# me433.net
KiCad netlist of a schematic drawn in EAGLE
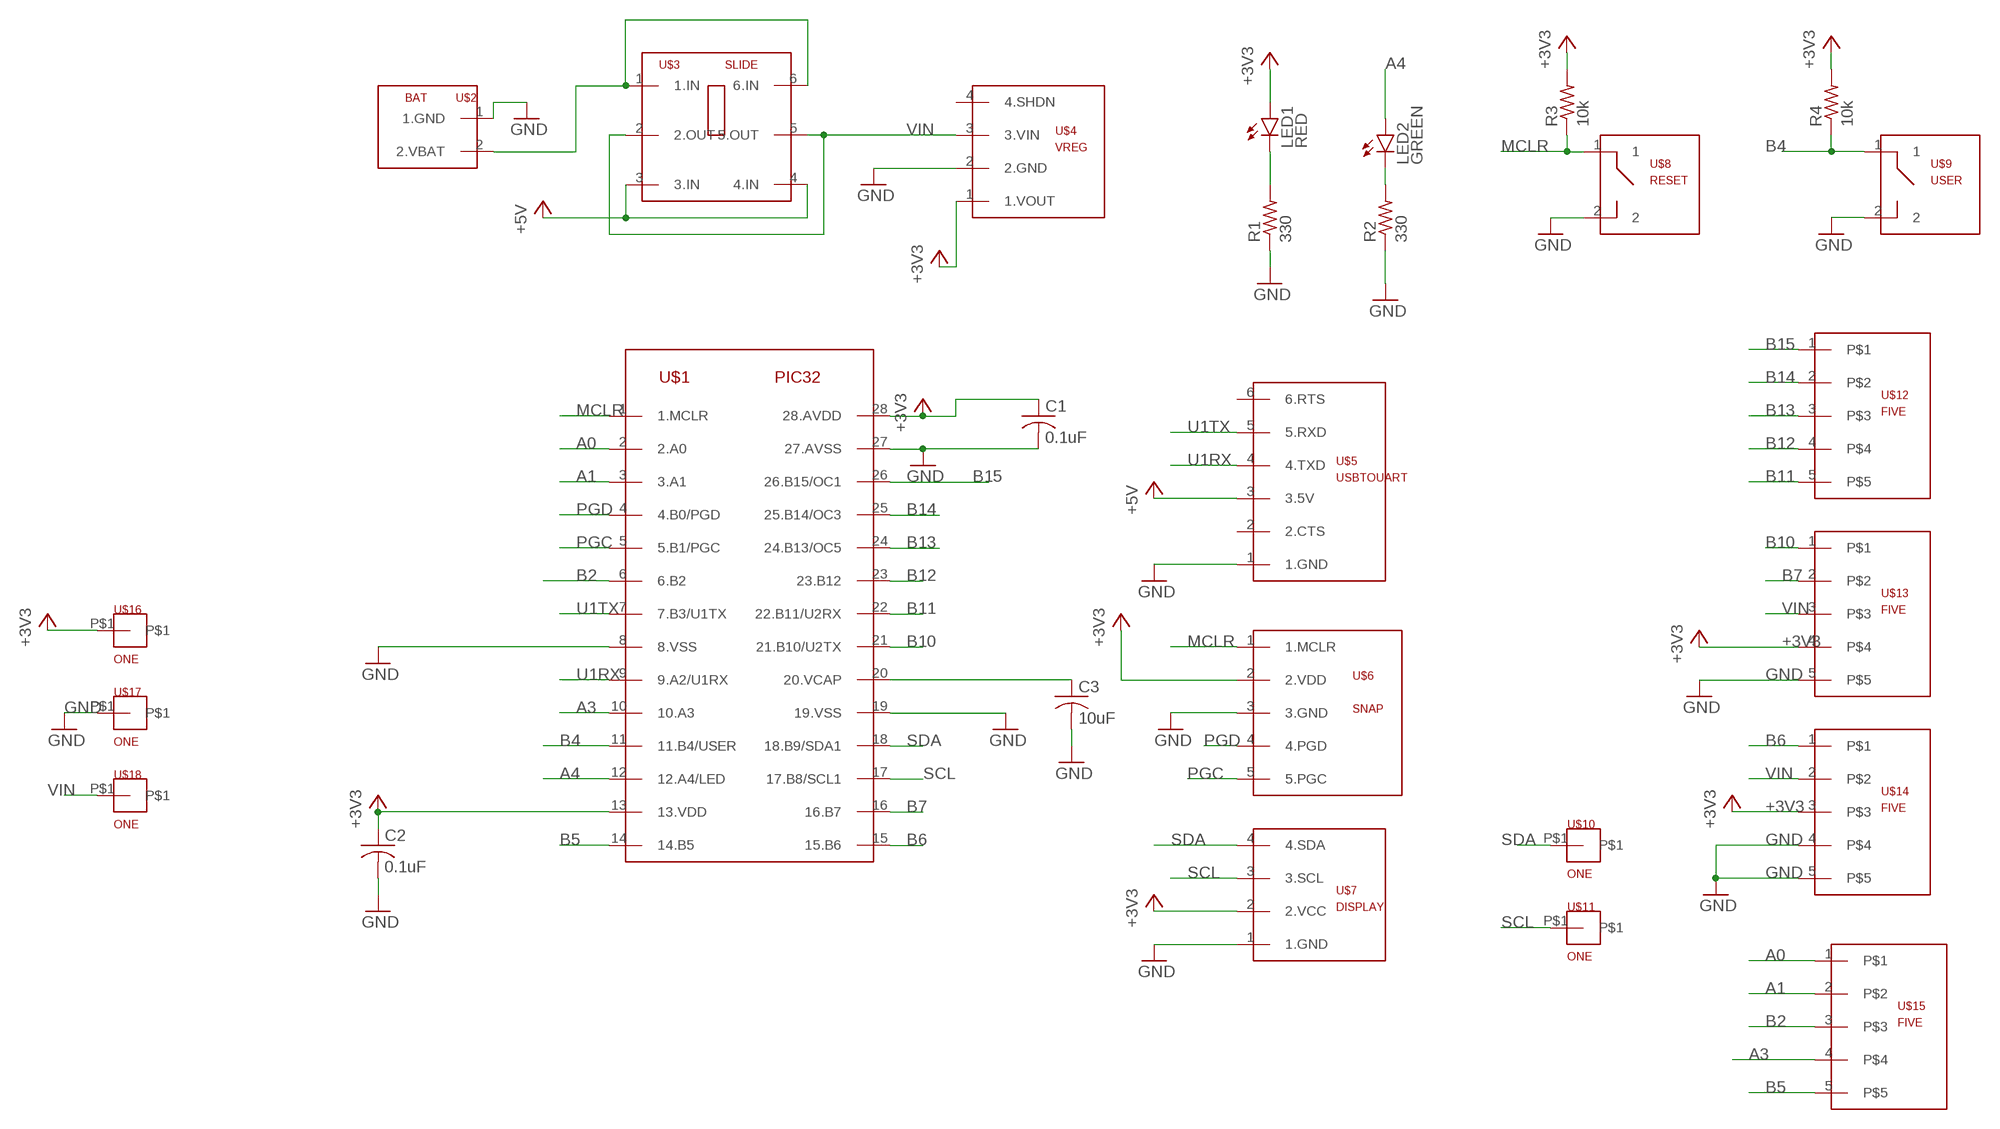
[diagram p0: schematic, sheet 1]

(export (version "E")
  (design (tool "Eeschema 10.0.6"))
  (components
    (comp (ref "C1")
      (value "0.1uF")
      (footprint "eagle-import:C025-024X044")
      (libsource (lib "eagle-import") (part "C-US025-024X044"))
    )
    (comp (ref "C2")
      (value "0.1uF")
      (footprint "eagle-import:C025-024X044")
      (libsource (lib "eagle-import") (part "C-US025-024X044"))
    )
    (comp (ref "C3")
      (value "10uF")
      (footprint "eagle-import:C025-024X044")
      (libsource (lib "eagle-import") (part "C-US025-024X044"))
    )
    (comp (ref "LED1")
      (value "RED")
      (footprint "eagle-import:LED3MM")
      (libsource (lib "eagle-import") (part "LED3MM"))
    )
    (comp (ref "LED2")
      (value "GREEN")
      (footprint "eagle-import:LED3MM")
      (libsource (lib "eagle-import") (part "LED3MM"))
    )
    (comp (ref "R1")
      (value "330")
      (footprint "eagle-import:0207_7")
      (libsource (lib "eagle-import") (part "R-US_0207/7"))
    )
    (comp (ref "R2")
      (value "330")
      (footprint "eagle-import:0207_7")
      (libsource (lib "eagle-import") (part "R-US_0207/7"))
    )
    (comp (ref "R3")
      (value "10k")
      (footprint "eagle-import:0207_7")
      (libsource (lib "eagle-import") (part "R-US_0207/7"))
    )
    (comp (ref "R4")
      (value "10k")
      (footprint "eagle-import:0207_7")
      (libsource (lib "eagle-import") (part "R-US_0207/7"))
    )
    (comp (ref "U$1")
      (value "PIC32")
      (footprint "eagle-import:DIL28-3")
      (libsource (lib "eagle-import") (part "PIC32"))
    )
    (comp (ref "U$2")
      (value "BAT")
      (footprint "eagle-import:BAT")
      (libsource (lib "eagle-import") (part "BAT"))
    )
    (comp (ref "U$3")
      (value "SLIDE")
      (footprint "eagle-import:SLIDE")
      (libsource (lib "eagle-import") (part "SLIDE"))
    )
    (comp (ref "U$4")
      (value "VREG")
      (footprint "eagle-import:VOLTAGEREG")
      (libsource (lib "eagle-import") (part "VREG"))
    )
    (comp (ref "U$5")
      (value "USBTOUART")
      (footprint "eagle-import:USBTOUART")
      (libsource (lib "eagle-import") (part "USBTOUART"))
    )
    (comp (ref "U$6")
      (value "SNAP")
      (footprint "eagle-import:SNAP")
      (libsource (lib "eagle-import") (part "SNAP"))
    )
    (comp (ref "U$7")
      (value "DISPLAY")
      (footprint "eagle-import:DISPLAY")
      (libsource (lib "eagle-import") (part "DISPLAY"))
    )
    (comp (ref "U$8")
      (value "RESET")
      (footprint "eagle-import:BUTTON")
      (libsource (lib "eagle-import") (part "BUTTON"))
    )
    (comp (ref "U$9")
      (value "USER")
      (footprint "eagle-import:BUTTON")
      (libsource (lib "eagle-import") (part "BUTTON"))
    )
    (comp (ref "U$10")
      (value "ONE")
      (footprint "eagle-import:ONE")
      (libsource (lib "eagle-import") (part "ONE"))
    )
    (comp (ref "U$11")
      (value "ONE")
      (footprint "eagle-import:ONE")
      (libsource (lib "eagle-import") (part "ONE"))
    )
    (comp (ref "U$12")
      (value "FIVE")
      (footprint "eagle-import:FIVE")
      (libsource (lib "eagle-import") (part "FIVE"))
    )
    (comp (ref "U$13")
      (value "FIVE")
      (footprint "eagle-import:FIVE")
      (libsource (lib "eagle-import") (part "FIVE"))
    )
    (comp (ref "U$14")
      (value "FIVE")
      (footprint "eagle-import:FIVE")
      (libsource (lib "eagle-import") (part "FIVE"))
    )
    (comp (ref "U$15")
      (value "FIVE")
      (footprint "eagle-import:FIVE")
      (libsource (lib "eagle-import") (part "FIVE"))
    )
    (comp (ref "U$16")
      (value "ONE")
      (footprint "eagle-import:ONE")
      (libsource (lib "eagle-import") (part "ONE"))
    )
    (comp (ref "U$17")
      (value "ONE")
      (footprint "eagle-import:ONE")
      (libsource (lib "eagle-import") (part "ONE"))
    )
    (comp (ref "U$18")
      (value "ONE")
      (footprint "eagle-import:ONE")
      (libsource (lib "eagle-import") (part "ONE"))
    )
  )
  (nets
    (net (code "1") (name "+3V3") (class "Default")
      (node (ref "C1") (pin "1") (pinfunction "1_1") (pintype "passive"))
      (node (ref "C2") (pin "1") (pinfunction "1_1") (pintype "passive"))
      (node (ref "LED1") (pin "A") (pinfunction "A_A") (pintype "passive"))
      (node (ref "R3") (pin "2") (pinfunction "2_2") (pintype "passive"))
      (node (ref "R4") (pin "2") (pinfunction "2_2") (pintype "passive"))
      (node (ref "U$1") (pin "13") (pinfunction "13.VDD_13") (pintype "bidirectional"))
      (node (ref "U$1") (pin "28") (pinfunction "28.AVDD_28") (pintype "bidirectional"))
      (node (ref "U$13") (pin "4") (pinfunction "P$4_4") (pintype "bidirectional"))
      (node (ref "U$14") (pin "3") (pinfunction "P$3_3") (pintype "bidirectional"))
      (node (ref "U$16") (pin "P$1") (pinfunction "P$1_P$1") (pintype "bidirectional"))
      (node (ref "U$4") (pin "1") (pinfunction "1.VOUT_1") (pintype "bidirectional"))
      (node (ref "U$6") (pin "2") (pinfunction "2.VDD_2") (pintype "bidirectional"))
      (node (ref "U$7") (pin "2") (pinfunction "2.VCC_2") (pintype "bidirectional"))
    )
    (net (code "2") (name "+5V") (class "Default")
      (node (ref "U$3") (pin "3") (pinfunction "3.IN_3") (pintype "bidirectional"))
      (node (ref "U$3") (pin "4") (pinfunction "4.IN_4") (pintype "bidirectional"))
      (node (ref "U$5") (pin "3") (pinfunction "3.5V_3") (pintype "bidirectional"))
    )
    (net (code "3") (name "/A0") (class "Default")
      (node (ref "U$1") (pin "2") (pinfunction "2.A0_2") (pintype "bidirectional"))
      (node (ref "U$15") (pin "1") (pinfunction "P$1_1") (pintype "bidirectional"))
    )
    (net (code "4") (name "/A1") (class "Default")
      (node (ref "U$1") (pin "3") (pinfunction "3.A1_3") (pintype "bidirectional"))
      (node (ref "U$15") (pin "2") (pinfunction "P$2_2") (pintype "bidirectional"))
    )
    (net (code "5") (name "/A3") (class "Default")
      (node (ref "U$1") (pin "10") (pinfunction "10.A3_10") (pintype "bidirectional"))
      (node (ref "U$15") (pin "4") (pinfunction "P$4_4") (pintype "bidirectional"))
    )
    (net (code "6") (name "/A4") (class "Default")
      (node (ref "LED2") (pin "A") (pinfunction "A_A") (pintype "passive"))
      (node (ref "U$1") (pin "12") (pinfunction "12.A4/LED_12") (pintype "bidirectional"))
    )
    (net (code "7") (name "/B2") (class "Default")
      (node (ref "U$1") (pin "6") (pinfunction "6.B2_6") (pintype "bidirectional"))
      (node (ref "U$15") (pin "3") (pinfunction "P$3_3") (pintype "bidirectional"))
    )
    (net (code "8") (name "/B4") (class "Default")
      (node (ref "R4") (pin "1") (pinfunction "1_1") (pintype "passive"))
      (node (ref "U$1") (pin "11") (pinfunction "11.B4/USER_11") (pintype "bidirectional"))
      (node (ref "U$9") (pin "1") (pinfunction "1_1") (pintype "bidirectional"))
    )
    (net (code "9") (name "/B5") (class "Default")
      (node (ref "U$1") (pin "14") (pinfunction "14.B5_14") (pintype "bidirectional"))
      (node (ref "U$15") (pin "5") (pinfunction "P$5_5") (pintype "bidirectional"))
    )
    (net (code "10") (name "/B6") (class "Default")
      (node (ref "U$1") (pin "15") (pinfunction "15.B6_15") (pintype "bidirectional"))
      (node (ref "U$14") (pin "1") (pinfunction "P$1_1") (pintype "bidirectional"))
    )
    (net (code "11") (name "/B7") (class "Default")
      (node (ref "U$1") (pin "16") (pinfunction "16.B7_16") (pintype "bidirectional"))
      (node (ref "U$13") (pin "2") (pinfunction "P$2_2") (pintype "bidirectional"))
    )
    (net (code "12") (name "/B10") (class "Default")
      (node (ref "U$1") (pin "21") (pinfunction "21.B10/U2TX_21") (pintype "bidirectional"))
      (node (ref "U$13") (pin "1") (pinfunction "P$1_1") (pintype "bidirectional"))
    )
    (net (code "13") (name "/B11") (class "Default")
      (node (ref "U$1") (pin "22") (pinfunction "22.B11/U2RX_22") (pintype "bidirectional"))
      (node (ref "U$12") (pin "5") (pinfunction "P$5_5") (pintype "bidirectional"))
    )
    (net (code "14") (name "/B12") (class "Default")
      (node (ref "U$1") (pin "23") (pinfunction "23.B12_23") (pintype "bidirectional"))
      (node (ref "U$12") (pin "4") (pinfunction "P$4_4") (pintype "bidirectional"))
    )
    (net (code "15") (name "/B13") (class "Default")
      (node (ref "U$1") (pin "24") (pinfunction "24.B13/OC5_24") (pintype "bidirectional"))
      (node (ref "U$12") (pin "3") (pinfunction "P$3_3") (pintype "bidirectional"))
    )
    (net (code "16") (name "/B14") (class "Default")
      (node (ref "U$1") (pin "25") (pinfunction "25.B14/OC3_25") (pintype "bidirectional"))
      (node (ref "U$12") (pin "2") (pinfunction "P$2_2") (pintype "bidirectional"))
    )
    (net (code "17") (name "/B15") (class "Default")
      (node (ref "U$1") (pin "26") (pinfunction "26.B15/OC1_26") (pintype "bidirectional"))
      (node (ref "U$12") (pin "1") (pinfunction "P$1_1") (pintype "bidirectional"))
    )
    (net (code "18") (name "/MCLR") (class "Default")
      (node (ref "R3") (pin "1") (pinfunction "1_1") (pintype "passive"))
      (node (ref "U$1") (pin "1") (pinfunction "1.MCLR_1") (pintype "bidirectional"))
      (node (ref "U$6") (pin "1") (pinfunction "1.MCLR_1") (pintype "bidirectional"))
      (node (ref "U$8") (pin "1") (pinfunction "1_1") (pintype "bidirectional"))
    )
    (net (code "19") (name "/PGC") (class "Default")
      (node (ref "U$1") (pin "5") (pinfunction "5.B1/PGC_5") (pintype "bidirectional"))
      (node (ref "U$6") (pin "5") (pinfunction "5.PGC_5") (pintype "bidirectional"))
    )
    (net (code "20") (name "/PGD") (class "Default")
      (node (ref "U$1") (pin "4") (pinfunction "4.B0/PGD_4") (pintype "bidirectional"))
      (node (ref "U$6") (pin "4") (pinfunction "4.PGD_4") (pintype "bidirectional"))
    )
    (net (code "21") (name "/SCL") (class "Default")
      (node (ref "U$1") (pin "17") (pinfunction "17.B8/SCL1_17") (pintype "bidirectional"))
      (node (ref "U$11") (pin "P$1") (pinfunction "P$1_P$1") (pintype "bidirectional"))
      (node (ref "U$7") (pin "3") (pinfunction "3.SCL_3") (pintype "bidirectional"))
    )
    (net (code "22") (name "/SDA") (class "Default")
      (node (ref "U$1") (pin "18") (pinfunction "18.B9/SDA1_18") (pintype "bidirectional"))
      (node (ref "U$10") (pin "P$1") (pinfunction "P$1_P$1") (pintype "bidirectional"))
      (node (ref "U$7") (pin "4") (pinfunction "4.SDA_4") (pintype "bidirectional"))
    )
    (net (code "23") (name "/U1RX") (class "Default")
      (node (ref "U$1") (pin "9") (pinfunction "9.A2/U1RX_9") (pintype "bidirectional"))
      (node (ref "U$5") (pin "4") (pinfunction "4.TXD_4") (pintype "bidirectional"))
    )
    (net (code "24") (name "/U1TX") (class "Default")
      (node (ref "U$1") (pin "7") (pinfunction "7.B3/U1TX_7") (pintype "bidirectional"))
      (node (ref "U$5") (pin "5") (pinfunction "5.RXD_5") (pintype "bidirectional"))
    )
    (net (code "25") (name "/VIN") (class "Default")
      (node (ref "U$13") (pin "3") (pinfunction "P$3_3") (pintype "bidirectional"))
      (node (ref "U$14") (pin "2") (pinfunction "P$2_2") (pintype "bidirectional"))
      (node (ref "U$18") (pin "P$1") (pinfunction "P$1_P$1") (pintype "bidirectional"))
      (node (ref "U$3") (pin "2") (pinfunction "2.OUT_2") (pintype "bidirectional"))
      (node (ref "U$3") (pin "5") (pinfunction "5.OUT_5") (pintype "bidirectional"))
      (node (ref "U$4") (pin "3") (pinfunction "3.VIN_3") (pintype "bidirectional"))
    )
    (net (code "26") (name "GND") (class "Default")
      (node (ref "C1") (pin "2") (pinfunction "2_2") (pintype "passive"))
      (node (ref "C2") (pin "2") (pinfunction "2_2") (pintype "passive"))
      (node (ref "C3") (pin "2") (pinfunction "2_2") (pintype "passive"))
      (node (ref "R1") (pin "1") (pinfunction "1_1") (pintype "passive"))
      (node (ref "R2") (pin "1") (pinfunction "1_1") (pintype "passive"))
      (node (ref "U$1") (pin "19") (pinfunction "19.VSS_19") (pintype "bidirectional"))
      (node (ref "U$1") (pin "27") (pinfunction "27.AVSS_27") (pintype "bidirectional"))
      (node (ref "U$1") (pin "8") (pinfunction "8.VSS_8") (pintype "bidirectional"))
      (node (ref "U$13") (pin "5") (pinfunction "P$5_5") (pintype "bidirectional"))
      (node (ref "U$14") (pin "4") (pinfunction "P$4_4") (pintype "bidirectional"))
      (node (ref "U$14") (pin "5") (pinfunction "P$5_5") (pintype "bidirectional"))
      (node (ref "U$17") (pin "P$1") (pinfunction "P$1_P$1") (pintype "bidirectional"))
      (node (ref "U$2") (pin "1") (pinfunction "1.GND_1") (pintype "bidirectional"))
      (node (ref "U$4") (pin "2") (pinfunction "2.GND_2") (pintype "bidirectional"))
      (node (ref "U$5") (pin "1") (pinfunction "1.GND_1") (pintype "bidirectional"))
      (node (ref "U$6") (pin "3") (pinfunction "3.GND_3") (pintype "bidirectional"))
      (node (ref "U$7") (pin "1") (pinfunction "1.GND_1") (pintype "bidirectional"))
      (node (ref "U$8") (pin "2") (pinfunction "2_2") (pintype "bidirectional"))
      (node (ref "U$9") (pin "2") (pinfunction "2_2") (pintype "bidirectional"))
    )
    (net (code "27") (name "Net-(LED1-C)") (class "Default")
      (node (ref "LED1") (pin "K") (pinfunction "C_K") (pintype "passive"))
      (node (ref "R1") (pin "2") (pinfunction "2_2") (pintype "passive"))
    )
    (net (code "28") (name "Net-(LED2-C)") (class "Default")
      (node (ref "LED2") (pin "K") (pinfunction "C_K") (pintype "passive"))
      (node (ref "R2") (pin "2") (pinfunction "2_2") (pintype "passive"))
    )
    (net (code "29") (name "Net-(U$1-20.VCAP)") (class "Default")
      (node (ref "C3") (pin "1") (pinfunction "1_1") (pintype "passive"))
      (node (ref "U$1") (pin "20") (pinfunction "20.VCAP_20") (pintype "bidirectional"))
    )
    (net (code "30") (name "Net-(U$2-2.VBAT)") (class "Default")
      (node (ref "U$2") (pin "2") (pinfunction "2.VBAT_2") (pintype "bidirectional"))
      (node (ref "U$3") (pin "1") (pinfunction "1.IN_1") (pintype "bidirectional"))
      (node (ref "U$3") (pin "6") (pinfunction "6.IN_6") (pintype "bidirectional"))
    )
    (net (code "31") (name "unconnected-(U$4-4.SHDN-Pad4)") (class "Default")
      (node (ref "U$4") (pin "4") (pinfunction "4.SHDN_4") (pintype "bidirectional"))
    )
    (net (code "32") (name "unconnected-(U$5-2.CTS-Pad2)") (class "Default")
      (node (ref "U$5") (pin "2") (pinfunction "2.CTS_2") (pintype "bidirectional"))
    )
    (net (code "33") (name "unconnected-(U$5-6.RTS-Pad6)") (class "Default")
      (node (ref "U$5") (pin "6") (pinfunction "6.RTS_6") (pintype "bidirectional"))
    )
  )
)
